# Trepanat_Power.net
KiCad netlist of a schematic drawn in Altium Designer
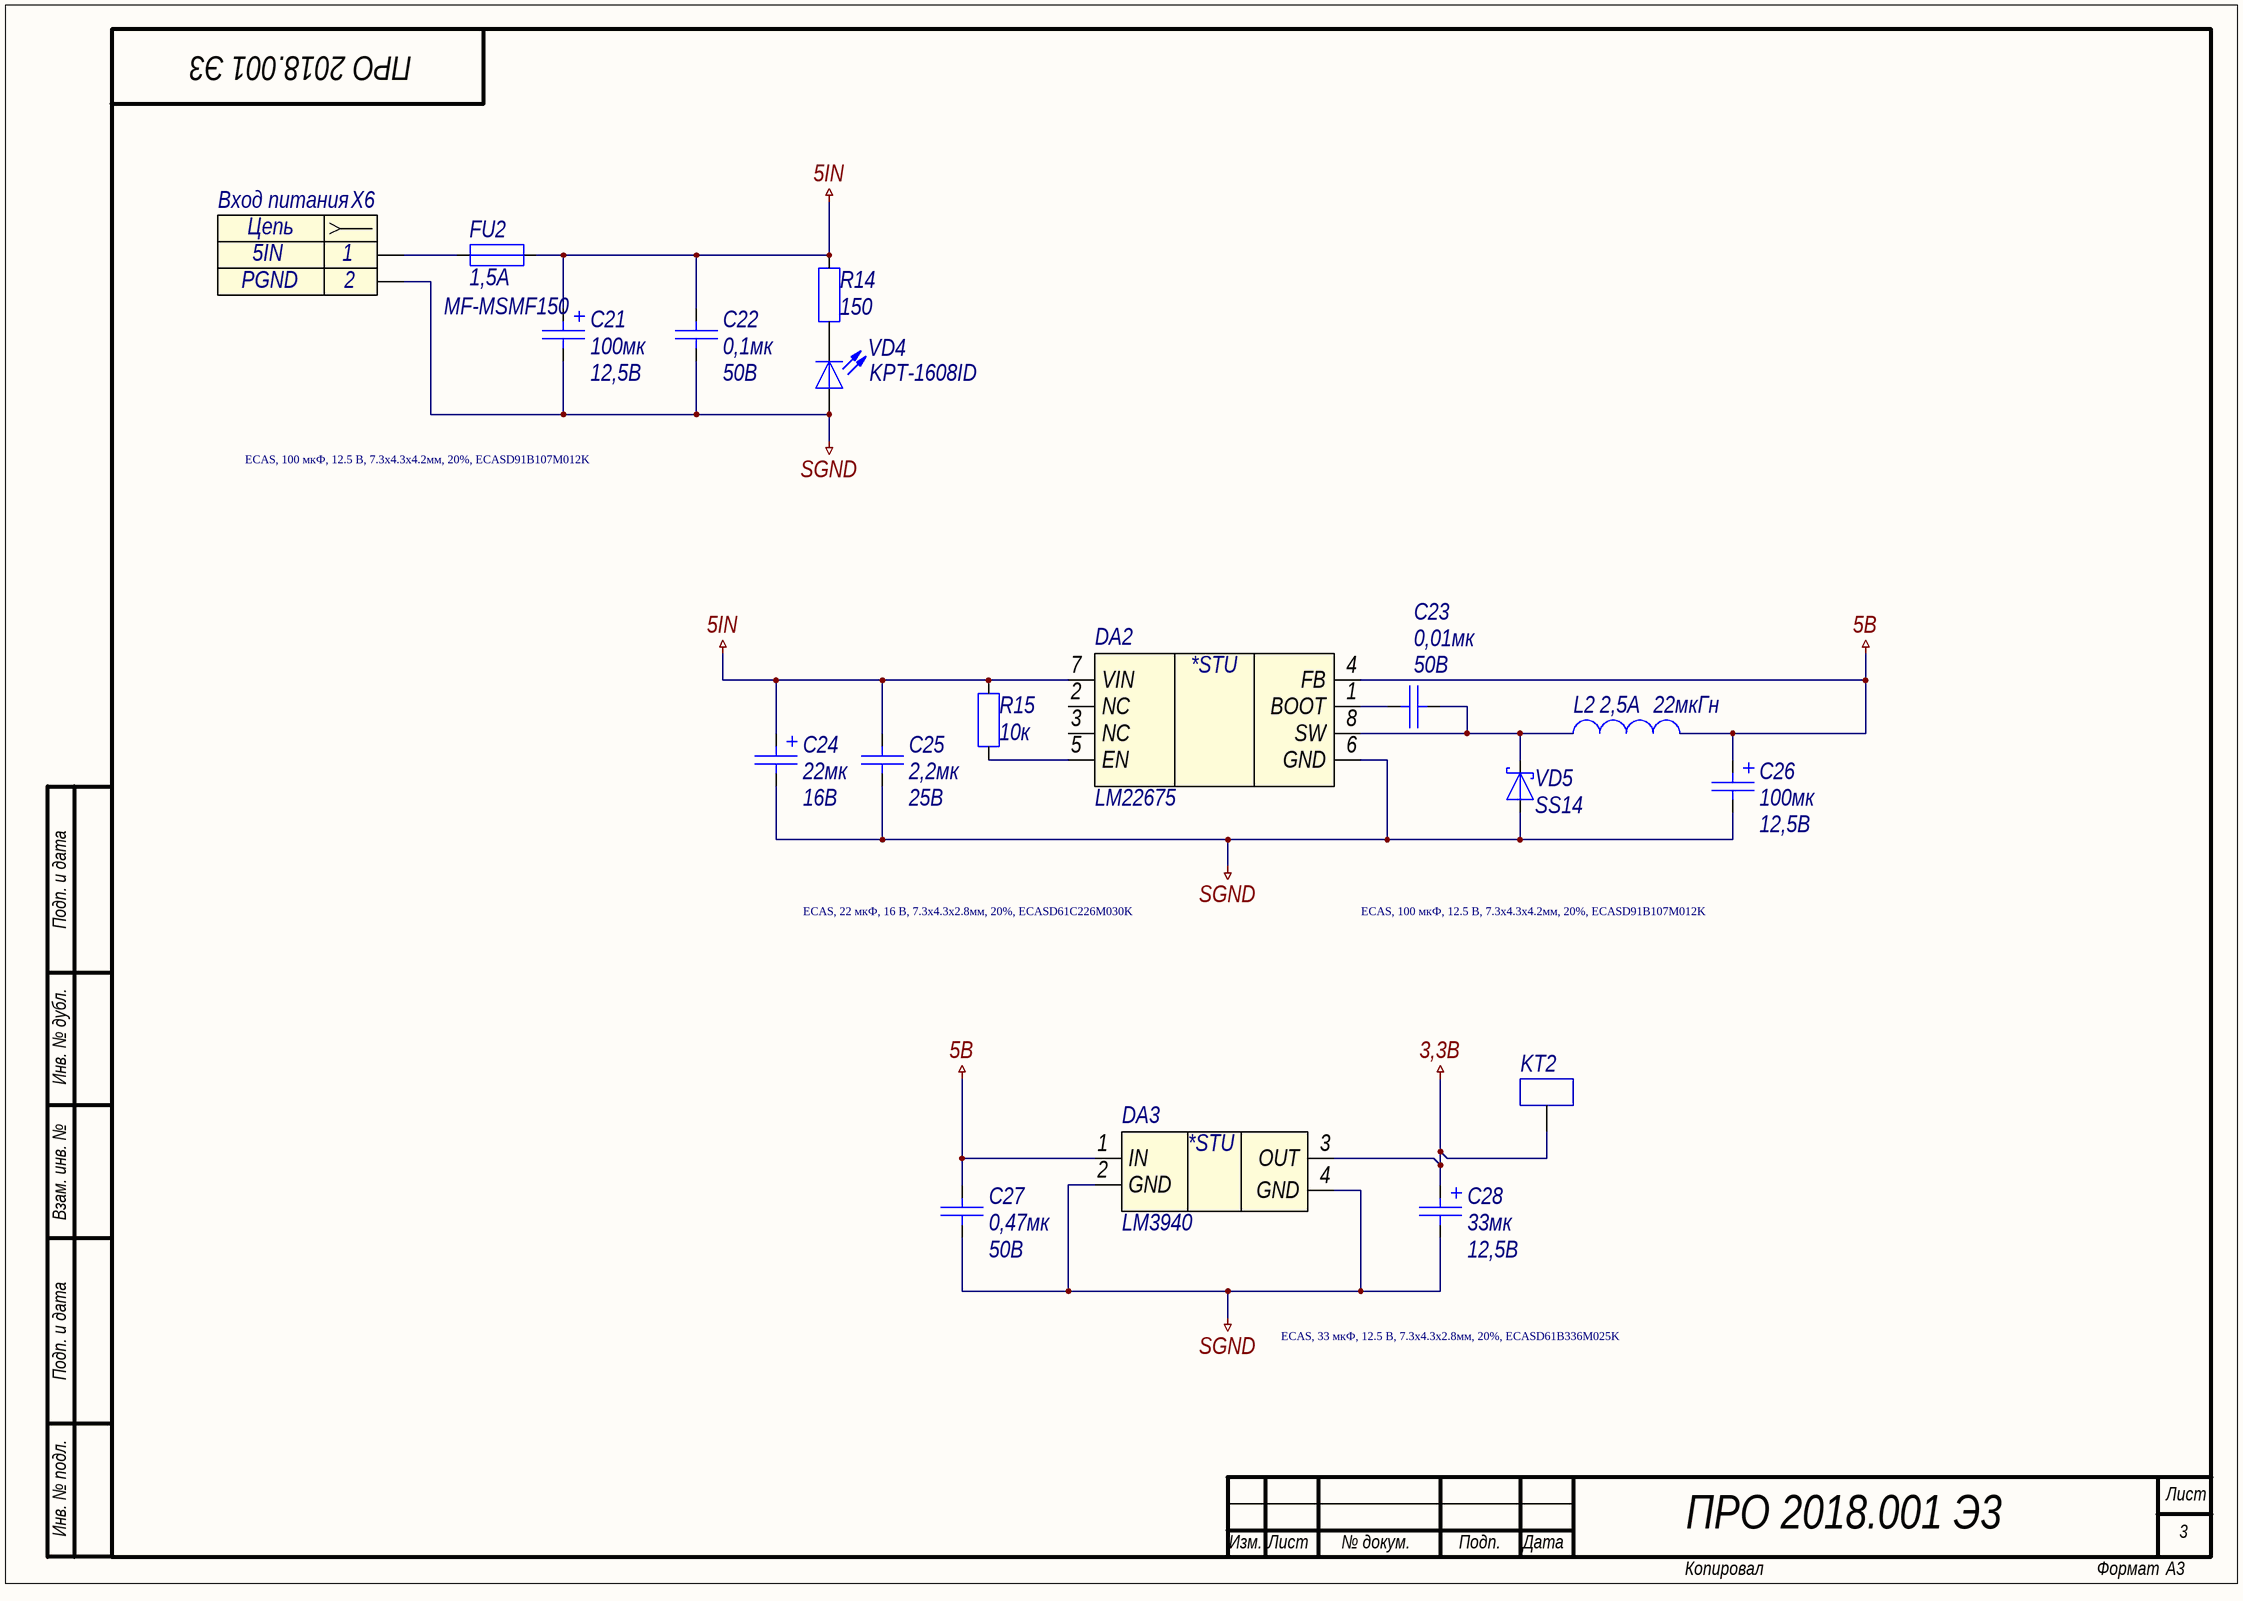
[diagram p0: Trepanat_Power.SchDoc]

(export (version "E")
  (design (tool "Eeschema 10.0.6"))
  (components
    (comp (ref "C21")
      (value "100мк")
      (footprint "ZabugorLib:TANTAL CASE D")
      (description "Конденсатор полярный")
      (fields (field (name "VOLTAGE") "12,5В"))
      (libsource (lib "ZabugorLib") (part "Capacitor_pol"))
    )
    (comp (ref "C22")
      (value "0,1мк")
      (footprint "ZabugorLib:C0805")
      (description "Конденсатор")
      (fields (field (name "VOLTAGE") "50В"))
      (libsource (lib "ZabugorLib") (part "Capacitor"))
    )
    (comp (ref "C23")
      (value "0,01мк")
      (footprint "ZabugorLib:C0805")
      (description "Конденсатор")
      (fields (field (name "VOLTAGE") "50В"))
      (libsource (lib "ZabugorLib") (part "Capacitor"))
    )
    (comp (ref "C24")
      (value "22мк")
      (footprint "ZabugorLib:TANTAL CASE D")
      (description "Конденсатор полярный")
      (fields (field (name "VOLTAGE") "16В"))
      (libsource (lib "ZabugorLib") (part "Capacitor_pol"))
    )
    (comp (ref "C25")
      (value "2,2мк")
      (footprint "ZabugorLib:C0805")
      (description "Конденсатор")
      (fields (field (name "VOLTAGE") "25В"))
      (libsource (lib "ZabugorLib") (part "Capacitor"))
    )
    (comp (ref "C26")
      (value "100мк")
      (footprint "ZabugorLib:TANTAL CASE D")
      (description "Конденсатор полярный")
      (fields (field (name "VOLTAGE") "12,5В"))
      (libsource (lib "ZabugorLib") (part "Capacitor_pol"))
    )
    (comp (ref "C27")
      (value "0,47мк")
      (footprint "ZabugorLib:C0805")
      (description "Конденсатор")
      (fields (field (name "VOLTAGE") "50В"))
      (libsource (lib "ZabugorLib") (part "Capacitor"))
    )
    (comp (ref "C28")
      (value "33мк")
      (footprint "ZabugorLib:TANTAL CASE D")
      (description "Конденсатор полярный")
      (fields (field (name "VOLTAGE") "12,5В"))
      (libsource (lib "ZabugorLib") (part "Capacitor_pol"))
    )
    (comp (ref "DA2")
      (value "LM22675")
      (footprint "ZabugorLib:SO PowerPAD-8")
      (description "3-A Step-Down Voltage Regulator")
      (libsource (lib "ZabugorLib") (part "LM22675"))
    )
    (comp (ref "DA3")
      (value "LM3940")
      (footprint "ZabugorLib:TO-263-3")
      (description "Low-Dropout Regulator for 5-V to 3.3-V Conversion")
      (libsource (lib "ZabugorLib") (part "LM3940"))
    )
    (comp (ref "FU2")
      (value "1,5A")
      (footprint "ZabugorLib:R1812")
      (description "Предохранитель")
      (fields (field (name "NAME") "MF-MSMF150") (field (name "Comment") "MF-MSMF150"))
      (libsource (lib "ZabugorLib") (part "Fuse"))
    )
    (comp (ref "KT2")
      (value "KT")
      (footprint "ZabugorLib:КТ")
      (description "Контрольная точка")
      (libsource (lib "ZabugorLib") (part "KT"))
    )
    (comp (ref "L2")
      (value "22мкГн")
      (footprint "ZabugorLib:IND_B82464G4223M")
      (description "Катушка индуктивности")
      (fields (field (name "IMAX") "2,5А"))
      (libsource (lib "ZabugorLib") (part "Inductor"))
    )
    (comp (ref "R14")
      (value "150")
      (footprint "ZabugorLib:R0805")
      (description "Резистор")
      (libsource (lib "ZabugorLib") (part "Resistor"))
    )
    (comp (ref "R15")
      (value "10к")
      (footprint "ZabugorLib:R0805")
      (description "Резистор")
      (libsource (lib "ZabugorLib") (part "Resistor"))
    )
    (comp (ref "VD4")
      (value "KPT-1608ID")
      (footprint "ZabugorLib:D0603")
      (description "Светодиод")
      (fields (field (name "NAME") "KPT-1608ID"))
      (libsource (lib "ZabugorLib") (part "LED_L"))
    )
    (comp (ref "VD5")
      (value "SS14")
      (footprint "ZabugorLib:SMA")
      (description "Диод Шоттки")
      (libsource (lib "ZabugorLib") (part "DiodeSchottky"))
    )
    (comp (ref "X6")
      (value "Вход питания")
      (footprint "ZabugorLib:DT-128V-2")
      (description "Разъем - 2 конт. розетка")
      (fields (field (name "NAME") "Вход питания"))
      (libsource (lib "ZabugorLib") (part "Header_2_sct"))
    )
  )
  (nets
    (net (code "1") (name "3,3B") (class "Default")
      (node (ref "C28") (pin "1") (pinfunction "1_1") (pintype "passive"))
      (node (ref "DA3") (pin "3") (pinfunction "OUT_3") (pintype "power_in"))
      (node (ref "KT2") (pin "1") (pinfunction "1_1") (pintype "passive"))
    )
    (net (code "2") (name "5B") (class "Default")
      (node (ref "C26") (pin "1") (pinfunction "1_1") (pintype "passive"))
      (node (ref "C27") (pin "2") (pinfunction "2_2") (pintype "passive"))
      (node (ref "DA2") (pin "4") (pinfunction "FB_4") (pintype "power_in"))
      (node (ref "DA3") (pin "1") (pinfunction "IN_1") (pintype "power_in"))
      (node (ref "L2") (pin "2") (pinfunction "2_2") (pintype "passive"))
    )
    (net (code "3") (name "5IN") (class "Default")
      (node (ref "C21") (pin "1") (pinfunction "1_1") (pintype "passive"))
      (node (ref "C22") (pin "2") (pinfunction "2_2") (pintype "passive"))
      (node (ref "C24") (pin "1") (pinfunction "1_1") (pintype "passive"))
      (node (ref "C25") (pin "2") (pinfunction "2_2") (pintype "passive"))
      (node (ref "DA2") (pin "7") (pinfunction "VIN_7") (pintype "power_in"))
      (node (ref "FU2") (pin "2") (pinfunction "2_2") (pintype "passive"))
      (node (ref "R14") (pin "1") (pinfunction "1_1") (pintype "passive"))
      (node (ref "R15") (pin "1") (pinfunction "1_1") (pintype "passive"))
    )
    (net (code "4") (name "Net-(DA2-BOOT)") (class "Default")
      (node (ref "C23") (pin "2") (pinfunction "2_2") (pintype "passive"))
      (node (ref "DA2") (pin "1") (pinfunction "BOOT_1") (pintype "power_in"))
    )
    (net (code "5") (name "Net-(DA2-EN)") (class "Default")
      (node (ref "DA2") (pin "5") (pinfunction "EN_5") (pintype "power_in"))
      (node (ref "R15") (pin "2") (pinfunction "2_2") (pintype "passive"))
    )
    (net (code "6") (name "Net-(DA2-SW)") (class "Default")
      (node (ref "C23") (pin "1") (pinfunction "1_1") (pintype "passive"))
      (node (ref "DA2") (pin "8") (pinfunction "SW_8") (pintype "power_in"))
      (node (ref "L2") (pin "1") (pinfunction "1_1") (pintype "passive"))
      (node (ref "VD5") (pin "1") (pinfunction "K_1") (pintype "passive"))
    )
    (net (code "7") (name "Net-(FU2-Pad1)") (class "Default")
      (node (ref "FU2") (pin "1") (pinfunction "1_1") (pintype "passive"))
      (node (ref "X6") (pin "1") (pinfunction "1_1") (pintype "passive"))
    )
    (net (code "8") (name "Net-(VD4-K)") (class "Default")
      (node (ref "R14") (pin "2") (pinfunction "2_2") (pintype "passive"))
      (node (ref "VD4") (pin "1") (pinfunction "K_1") (pintype "passive"))
    )
    (net (code "9") (name "SGND") (class "Default")
      (node (ref "C21") (pin "2") (pinfunction "2_2") (pintype "passive"))
      (node (ref "C22") (pin "1") (pinfunction "1_1") (pintype "passive"))
      (node (ref "C24") (pin "2") (pinfunction "2_2") (pintype "passive"))
      (node (ref "C25") (pin "1") (pinfunction "1_1") (pintype "passive"))
      (node (ref "C26") (pin "2") (pinfunction "2_2") (pintype "passive"))
      (node (ref "C27") (pin "1") (pinfunction "1_1") (pintype "passive"))
      (node (ref "C28") (pin "2") (pinfunction "2_2") (pintype "passive"))
      (node (ref "DA2") (pin "6") (pinfunction "GND_6") (pintype "power_in"))
      (node (ref "DA3") (pin "2") (pinfunction "GND_2") (pintype "power_in"))
      (node (ref "DA3") (pin "4") (pinfunction "GND_4") (pintype "power_in"))
      (node (ref "VD4") (pin "2") (pinfunction "A_2") (pintype "passive"))
      (node (ref "VD5") (pin "2") (pinfunction "A_2") (pintype "passive"))
      (node (ref "X6") (pin "2") (pinfunction "2_2") (pintype "passive"))
    )
    (net (code "10") (name "unconnected-(DA2-NC-Pad2)") (class "Default")
      (node (ref "DA2") (pin "2") (pinfunction "NC_2") (pintype "power_in"))
    )
    (net (code "11") (name "unconnected-(DA2-NC-Pad3)") (class "Default")
      (node (ref "DA2") (pin "3") (pinfunction "NC_3") (pintype "power_in"))
    )
  )
)
